# STM32F103_PCB.net
KiCad netlist of a schematic drawn in EAGLE
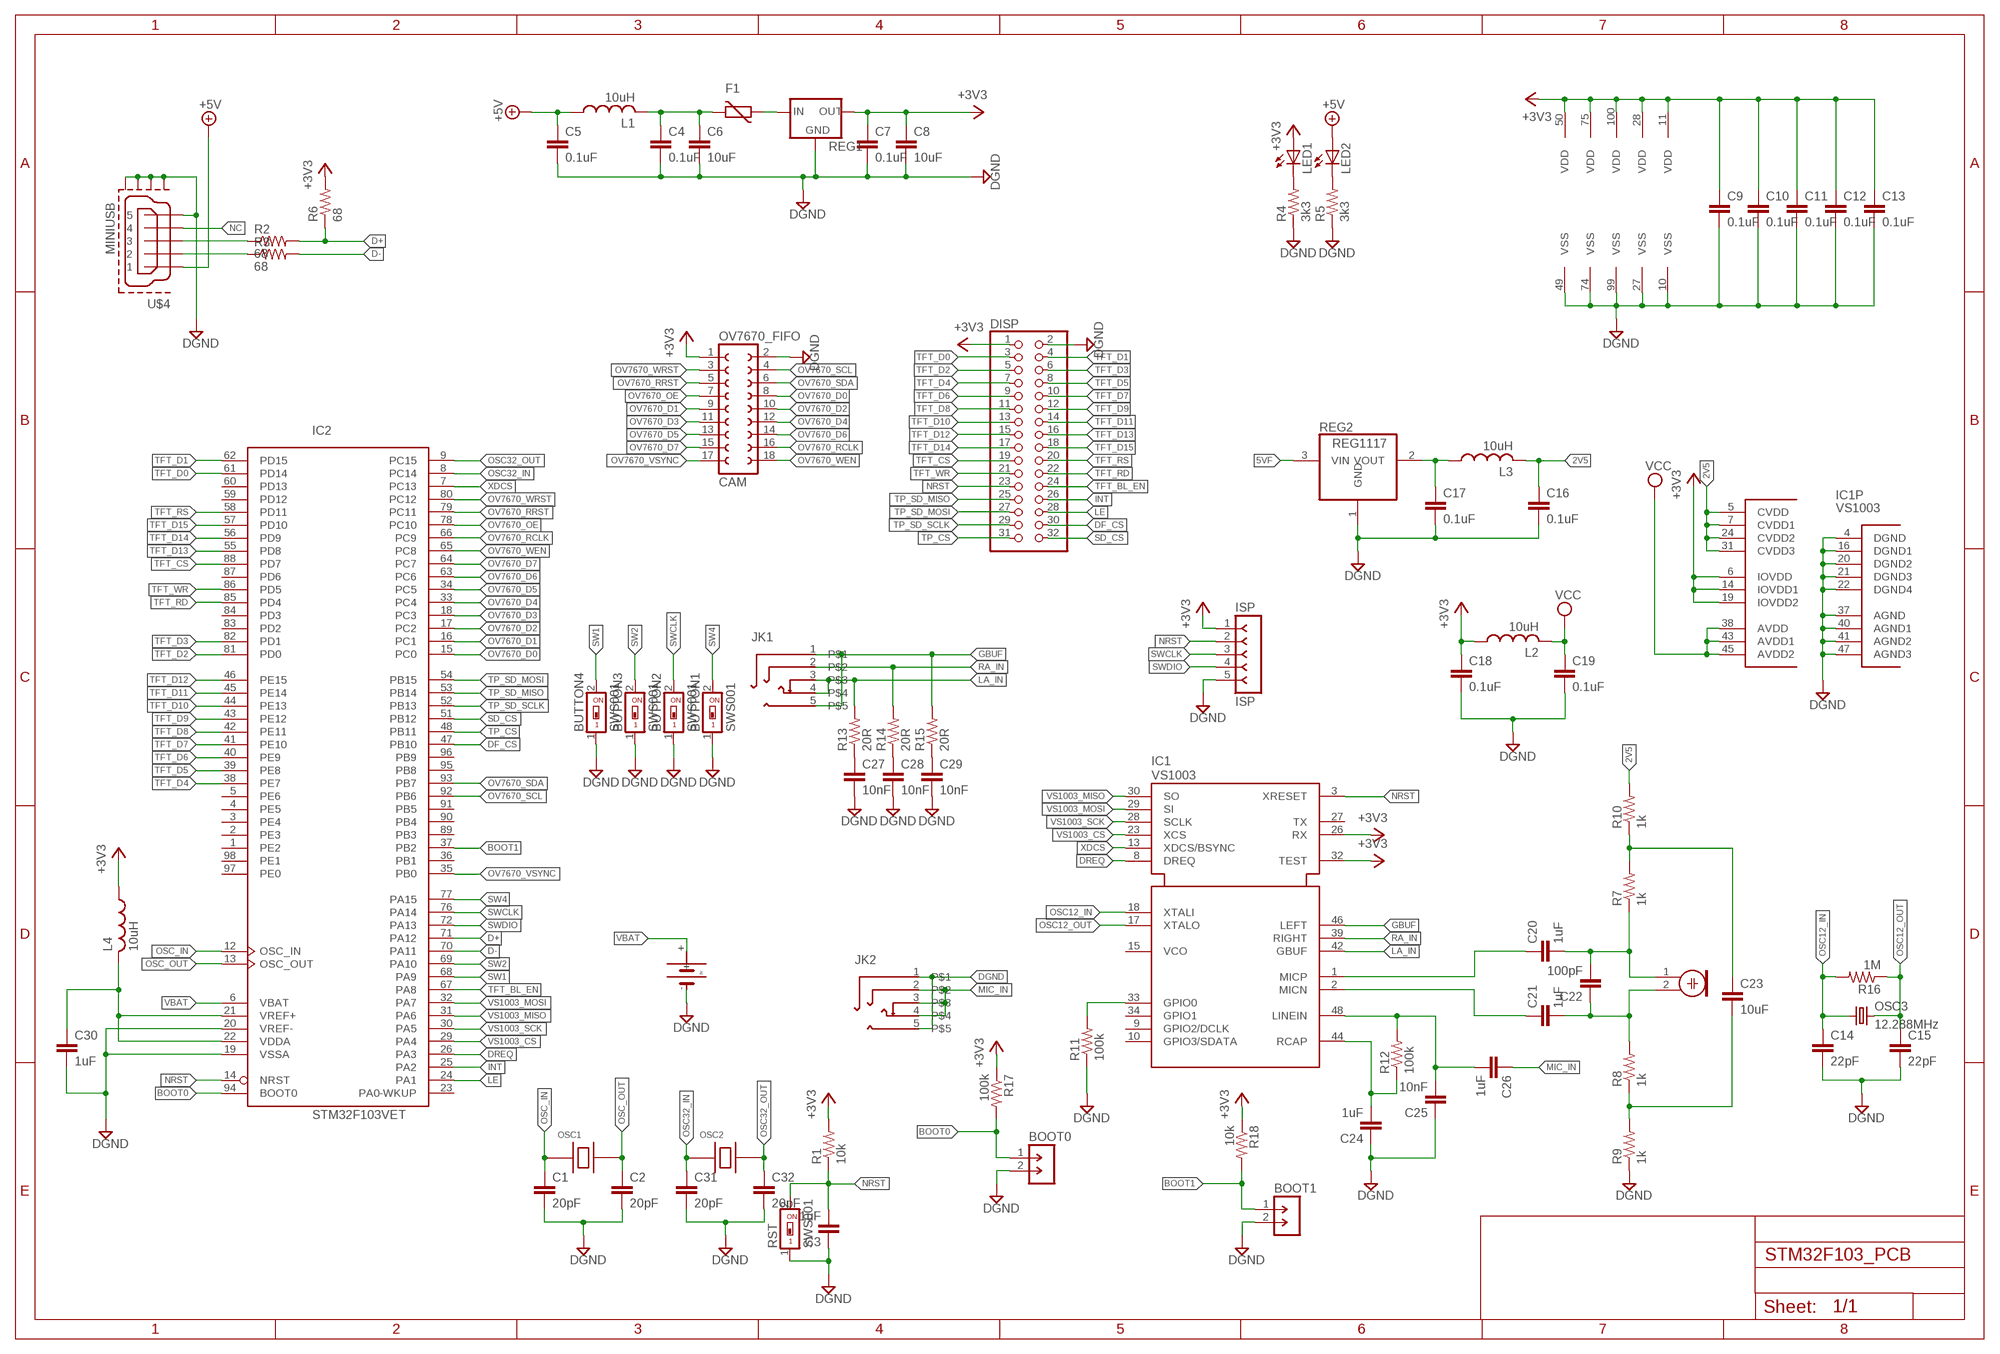
[diagram p0: schematic, sheet 1]

(export (version "E")
  (design (tool "Eeschema 10.0.6"))
  (components
    (comp (ref "BOOT0")
      (value "M-1X02-SIP-100-32")
      (footprint "eagle-import:SIP-100-02-32")
      (libsource (lib "eagle-import") (part "M-1X02-SIP-100-32"))
    )
    (comp (ref "BOOT1")
      (value "M-1X02-SIP-100-32")
      (footprint "eagle-import:SIP-100-02-32")
      (libsource (lib "eagle-import") (part "M-1X02-SIP-100-32"))
    )
    (comp (ref "BUTTON1")
      (value "SWS001")
      (footprint "eagle-import:SMS-001")
      (libsource (lib "eagle-import") (part "SWS001"))
    )
    (comp (ref "BUTTON2")
      (value "SWS001")
      (footprint "eagle-import:SMS-001")
      (libsource (lib "eagle-import") (part "SWS001"))
    )
    (comp (ref "BUTTON3")
      (value "SWS001")
      (footprint "eagle-import:SMS-001")
      (libsource (lib "eagle-import") (part "SWS001"))
    )
    (comp (ref "BUTTON4")
      (value "SWS001")
      (footprint "eagle-import:SMS-001")
      (libsource (lib "eagle-import") (part "SWS001"))
    )
    (comp (ref "C1")
      (value "20pF")
      (footprint "eagle-import:C1206")
      (libsource (lib "eagle-import") (part "C-EUC1206"))
    )
    (comp (ref "C2")
      (value "20pF")
      (footprint "eagle-import:C1206")
      (libsource (lib "eagle-import") (part "C-EUC1206"))
    )
    (comp (ref "C3")
      (value "1uF")
      (footprint "eagle-import:C1206")
      (libsource (lib "eagle-import") (part "C-EUC1206"))
    )
    (comp (ref "C4")
      (value "0.1uF")
      (footprint "eagle-import:C1206")
      (libsource (lib "eagle-import") (part "C-EUC1206"))
    )
    (comp (ref "C5")
      (value "0.1uF")
      (footprint "eagle-import:C1206")
      (libsource (lib "eagle-import") (part "C-EUC1206"))
    )
    (comp (ref "C6")
      (value "10uF")
      (footprint "eagle-import:C1206")
      (libsource (lib "eagle-import") (part "C-EUC1206"))
    )
    (comp (ref "C7")
      (value "0.1uF")
      (footprint "eagle-import:C1206")
      (libsource (lib "eagle-import") (part "C-EUC1206"))
    )
    (comp (ref "C8")
      (value "10uF")
      (footprint "eagle-import:C1206")
      (libsource (lib "eagle-import") (part "C-EUC1206"))
    )
    (comp (ref "C9")
      (value "0.1uF")
      (footprint "eagle-import:C1206")
      (libsource (lib "eagle-import") (part "C-EUC1206"))
    )
    (comp (ref "C10")
      (value "0.1uF")
      (footprint "eagle-import:C1206")
      (libsource (lib "eagle-import") (part "C-EUC1206"))
    )
    (comp (ref "C11")
      (value "0.1uF")
      (footprint "eagle-import:C1206")
      (libsource (lib "eagle-import") (part "C-EUC1206"))
    )
    (comp (ref "C12")
      (value "0.1uF")
      (footprint "eagle-import:C1206")
      (libsource (lib "eagle-import") (part "C-EUC1206"))
    )
    (comp (ref "C13")
      (value "0.1uF")
      (footprint "eagle-import:C1206")
      (libsource (lib "eagle-import") (part "C-EUC1206"))
    )
    (comp (ref "C14")
      (value "22pF")
      (footprint "eagle-import:C1206")
      (libsource (lib "eagle-import") (part "C-EUC1206"))
    )
    (comp (ref "C15")
      (value "22pF")
      (footprint "eagle-import:C1206")
      (libsource (lib "eagle-import") (part "C-EUC1206"))
    )
    (comp (ref "C16")
      (value "0.1uF")
      (footprint "eagle-import:C1206")
      (libsource (lib "eagle-import") (part "C-EUC1206"))
    )
    (comp (ref "C17")
      (value "0.1uF")
      (footprint "eagle-import:C1206")
      (libsource (lib "eagle-import") (part "C-EUC1206"))
    )
    (comp (ref "C18")
      (value "0.1uF")
      (footprint "eagle-import:C1206")
      (libsource (lib "eagle-import") (part "C-EUC1206"))
    )
    (comp (ref "C19")
      (value "0.1uF")
      (footprint "eagle-import:C1206")
      (libsource (lib "eagle-import") (part "C-EUC1206"))
    )
    (comp (ref "C20")
      (value "1uF")
      (footprint "eagle-import:C1206")
      (libsource (lib "eagle-import") (part "C-EUC1206"))
    )
    (comp (ref "C21")
      (value "1uF")
      (footprint "eagle-import:C1206")
      (libsource (lib "eagle-import") (part "C-EUC1206"))
    )
    (comp (ref "C22")
      (value "100pF")
      (footprint "eagle-import:C1206")
      (libsource (lib "eagle-import") (part "C-EUC1206"))
    )
    (comp (ref "C23")
      (value "10uF")
      (footprint "eagle-import:C1206")
      (libsource (lib "eagle-import") (part "C-EUC1206"))
    )
    (comp (ref "C24")
      (value "1uF")
      (footprint "eagle-import:C1206")
      (libsource (lib "eagle-import") (part "C-EUC1206"))
    )
    (comp (ref "C25")
      (value "10nF")
      (footprint "eagle-import:C1206")
      (libsource (lib "eagle-import") (part "C-EUC1206"))
    )
    (comp (ref "C26")
      (value "1uF")
      (footprint "eagle-import:C1206")
      (libsource (lib "eagle-import") (part "C-EUC1206"))
    )
    (comp (ref "C27")
      (value "10nF")
      (footprint "eagle-import:C1206")
      (libsource (lib "eagle-import") (part "C-EUC1206"))
    )
    (comp (ref "C28")
      (value "10nF")
      (footprint "eagle-import:C1206")
      (libsource (lib "eagle-import") (part "C-EUC1206"))
    )
    (comp (ref "C29")
      (value "10nF")
      (footprint "eagle-import:C1206")
      (libsource (lib "eagle-import") (part "C-EUC1206"))
    )
    (comp (ref "C30")
      (value "1uF")
      (footprint "eagle-import:C1206")
      (libsource (lib "eagle-import") (part "C-EUC1206"))
    )
    (comp (ref "C31")
      (value "20pF")
      (footprint "eagle-import:C1206")
      (libsource (lib "eagle-import") (part "C-EUC1206"))
    )
    (comp (ref "C32")
      (value "20pF")
      (footprint "eagle-import:C1206")
      (libsource (lib "eagle-import") (part "C-EUC1206"))
    )
    (comp (ref "CAM")
      (value "OV7670_FIFO")
      (footprint "eagle-import:FE09-2")
      (libsource (lib "eagle-import") (part "FE09-2"))
    )
    (comp (ref "DISP")
      (value "PINHD-2X16")
      (footprint "eagle-import:2X16")
      (libsource (lib "eagle-import") (part "PINHD-2X16"))
    )
    (comp (ref "F1")
      (value "VARISTORCN1206")
      (footprint "eagle-import:CT_CN1206")
      (libsource (lib "eagle-import") (part "VARISTORCN1206"))
    )
    (comp (ref "IC1")
      (value "VS1003")
      (footprint "eagle-import:LQFP48")
      (libsource (lib "eagle-import") (part "VS1003"))
    )
    (comp (ref "IC2")
      (value "STM32F103VET")
      (footprint "eagle-import:LQFP100")
      (libsource (lib "eagle-import") (part "STM32F103VTE"))
    )
    (comp (ref "ISP")
      (value "ISP")
      (footprint "eagle-import:SIP-100-05-40")
      (libsource (lib "eagle-import") (part "F-1X05-SIP-100-40"))
    )
    (comp (ref "JK1")
      (value "HEADPHONE_XXX1")
      (footprint "eagle-import:HEADPHONE_XXX1")
      (libsource (lib "eagle-import") (part "HEADPHONE_XXX1"))
    )
    (comp (ref "JK2")
      (value "HEADPHONE_XXX1")
      (footprint "eagle-import:HEADPHONE_XXX1")
      (libsource (lib "eagle-import") (part "HEADPHONE_XXX1"))
    )
    (comp (ref "L1")
      (value "10uH")
      (footprint "eagle-import:L3216C")
      (libsource (lib "eagle-import") (part "L-USL3216C"))
    )
    (comp (ref "L2")
      (value "10uH")
      (footprint "eagle-import:L3216C")
      (libsource (lib "eagle-import") (part "L-USL3216C"))
    )
    (comp (ref "L3")
      (value "10uH")
      (footprint "eagle-import:L3216C")
      (libsource (lib "eagle-import") (part "L-USL3216C"))
    )
    (comp (ref "L4")
      (value "10uH")
      (footprint "eagle-import:L3216C")
      (libsource (lib "eagle-import") (part "L-USL3216C"))
    )
    (comp (ref "LED1")
      (value "LEDSML1206")
      (footprint "eagle-import:SML1206")
      (libsource (lib "eagle-import") (part "LEDSML1206"))
    )
    (comp (ref "LED2")
      (value "LEDSML1206")
      (footprint "eagle-import:SML1206")
      (libsource (lib "eagle-import") (part "LEDSML1206"))
    )
    (comp (ref "MIC")
      (value "ELECTRET_MICROPHON-WM-61A")
      (footprint "eagle-import:WM-61A")
      (libsource (lib "eagle-import") (part "ELECTRET_MICROPHON-WM-61A"))
    )
    (comp (ref "OSC1")
      (value "8.0MHz")
      (footprint "eagle-import:IQG7050B")
      (libsource (lib "eagle-import") (part "SMCE-7050"))
    )
    (comp (ref "OSC2")
      (value "32.768kHz")
      (footprint "eagle-import:IQG5032A")
      (libsource (lib "eagle-import") (part "SMAQ-5032A"))
    )
    (comp (ref "OSC3")
      (value "12.288MHz")
      (footprint "eagle-import:HC49UP")
      (libsource (lib "eagle-import") (part "CRYSTALHC49UP"))
    )
    (comp (ref "R1")
      (value "10k")
      (footprint "eagle-import:R1206")
      (libsource (lib "eagle-import") (part "R-US_R1206"))
    )
    (comp (ref "R2")
      (value "68")
      (footprint "eagle-import:R1206")
      (libsource (lib "eagle-import") (part "R-US_R1206"))
    )
    (comp (ref "R3")
      (value "68")
      (footprint "eagle-import:R1206")
      (libsource (lib "eagle-import") (part "R-US_R1206"))
    )
    (comp (ref "R4")
      (value "3k3")
      (footprint "eagle-import:R1206")
      (libsource (lib "eagle-import") (part "R-US_R1206"))
    )
    (comp (ref "R5")
      (value "3k3")
      (footprint "eagle-import:R1206")
      (libsource (lib "eagle-import") (part "R-US_R1206"))
    )
    (comp (ref "R6")
      (value "68")
      (footprint "eagle-import:R1206")
      (libsource (lib "eagle-import") (part "R-US_R1206"))
    )
    (comp (ref "R7")
      (value "1k")
      (footprint "eagle-import:R1206")
      (libsource (lib "eagle-import") (part "R-US_R1206"))
    )
    (comp (ref "R8")
      (value "1k")
      (footprint "eagle-import:R1206")
      (libsource (lib "eagle-import") (part "R-US_R1206"))
    )
    (comp (ref "R9")
      (value "1k")
      (footprint "eagle-import:R1206")
      (libsource (lib "eagle-import") (part "R-US_R1206"))
    )
    (comp (ref "R10")
      (value "1k")
      (footprint "eagle-import:R1206")
      (libsource (lib "eagle-import") (part "R-US_R1206"))
    )
    (comp (ref "R11")
      (value "100k")
      (footprint "eagle-import:R1206")
      (libsource (lib "eagle-import") (part "R-US_R1206"))
    )
    (comp (ref "R12")
      (value "100k")
      (footprint "eagle-import:R1206")
      (libsource (lib "eagle-import") (part "R-US_R1206"))
    )
    (comp (ref "R13")
      (value "20R")
      (footprint "eagle-import:R1206")
      (libsource (lib "eagle-import") (part "R-US_R1206"))
    )
    (comp (ref "R14")
      (value "20R")
      (footprint "eagle-import:R1206")
      (libsource (lib "eagle-import") (part "R-US_R1206"))
    )
    (comp (ref "R15")
      (value "20R")
      (footprint "eagle-import:R1206")
      (libsource (lib "eagle-import") (part "R-US_R1206"))
    )
    (comp (ref "R16")
      (value "1M")
      (footprint "eagle-import:R1206")
      (libsource (lib "eagle-import") (part "R-US_R1206"))
    )
    (comp (ref "R17")
      (value "100k")
      (footprint "eagle-import:R1206")
      (libsource (lib "eagle-import") (part "R-US_R1206"))
    )
    (comp (ref "R18")
      (value "10k")
      (footprint "eagle-import:R1206")
      (libsource (lib "eagle-import") (part "R-US_R1206"))
    )
    (comp (ref "REG1")
      (value "XC63FPM")
      (footprint "eagle-import:SOT23")
      (libsource (lib "eagle-import") (part "XC63FPM"))
    )
    (comp (ref "REG2")
      (value "REG1117")
      (footprint "eagle-import:SOT223")
      (libsource (lib "eagle-import") (part "REG1117"))
    )
    (comp (ref "RST")
      (value "SWS001")
      (footprint "eagle-import:SMS-001")
      (libsource (lib "eagle-import") (part "SWS001"))
    )
    (comp (ref "U$1")
      (value "1220BATTERY_SF")
      (footprint "eagle-import:1220BATTERY")
      (libsource (lib "eagle-import") (part "1220BATTERY_SF"))
    )
    (comp (ref "U$4")
      (value "MINIUSB")
      (footprint "eagle-import:MK5P")
      (libsource (lib "eagle-import") (part "MINIUSB"))
    )
  )
  (nets
    (net (code "1") (name "+3V3") (class "Default")
      (node (ref "C10") (pin "1") (pinfunction "1_1") (pintype "passive"))
      (node (ref "C11") (pin "1") (pinfunction "1_1") (pintype "passive"))
      (node (ref "C12") (pin "1") (pinfunction "1_1") (pintype "passive"))
      (node (ref "C13") (pin "1") (pinfunction "1_1") (pintype "passive"))
      (node (ref "C18") (pin "1") (pinfunction "1_1") (pintype "passive"))
      (node (ref "C7") (pin "1") (pinfunction "1_1") (pintype "passive"))
      (node (ref "C8") (pin "1") (pinfunction "1_1") (pintype "passive"))
      (node (ref "C9") (pin "1") (pinfunction "1_1") (pintype "passive"))
      (node (ref "CAM") (pin "1") (pinfunction "1_1") (pintype "passive"))
      (node (ref "DISP") (pin "1") (pinfunction "1_1") (pintype "passive"))
      (node (ref "IC1") (pin "14") (pinfunction "IOVDD1_14") (pintype "power_in"))
      (node (ref "IC1") (pin "19") (pinfunction "IOVDD2_19") (pintype "power_in"))
      (node (ref "IC1") (pin "26") (pinfunction "RX_26") (pintype "bidirectional"))
      (node (ref "IC1") (pin "32") (pinfunction "TEST_32") (pintype "bidirectional"))
      (node (ref "IC1") (pin "6") (pinfunction "IOVDD_6") (pintype "power_in"))
      (node (ref "IC2") (pin "100") (pinfunction "VDD_100") (pintype "power_in"))
      (node (ref "IC2") (pin "11") (pinfunction "VDD_11") (pintype "power_in"))
      (node (ref "IC2") (pin "28") (pinfunction "VDD_28") (pintype "power_in"))
      (node (ref "IC2") (pin "50") (pinfunction "VDD_50") (pintype "power_in"))
      (node (ref "IC2") (pin "75") (pinfunction "VDD_75") (pintype "power_in"))
      (node (ref "ISP") (pin "1") (pinfunction "1_1") (pintype "passive"))
      (node (ref "L2") (pin "1") (pinfunction "1_1") (pintype "passive"))
      (node (ref "L4") (pin "1") (pinfunction "1_1") (pintype "passive"))
      (node (ref "LED1") (pin "A") (pinfunction "A_A") (pintype "passive"))
      (node (ref "R1") (pin "2") (pinfunction "2_2") (pintype "passive"))
      (node (ref "R17") (pin "1") (pinfunction "1_1") (pintype "passive"))
      (node (ref "R18") (pin "1") (pinfunction "1_1") (pintype "passive"))
      (node (ref "R6") (pin "2") (pinfunction "2_2") (pintype "passive"))
      (node (ref "REG1") (pin "2") (pinfunction "OUT_2") (pintype "passive"))
    )
    (net (code "2") (name "+5V") (class "Default")
      (node (ref "C5") (pin "1") (pinfunction "1_1") (pintype "passive"))
      (node (ref "L1") (pin "1") (pinfunction "1_1") (pintype "passive"))
      (node (ref "LED2") (pin "A") (pinfunction "A_A") (pintype "passive"))
      (node (ref "U$4") (pin "1") (pinfunction "1_1") (pintype "input"))
    )
    (net (code "3") (name "2V5") (class "Default")
      (node (ref "C16") (pin "1") (pinfunction "1_1") (pintype "passive"))
      (node (ref "IC1") (pin "24") (pinfunction "CVDD2_24") (pintype "power_in"))
      (node (ref "IC1") (pin "31") (pinfunction "CVDD3_31") (pintype "power_in"))
      (node (ref "IC1") (pin "5") (pinfunction "CVDD_5") (pintype "power_in"))
      (node (ref "IC1") (pin "7") (pinfunction "CVDD1_7") (pintype "power_in"))
      (node (ref "L3") (pin "2") (pinfunction "2_2") (pintype "passive"))
      (node (ref "R10") (pin "2") (pinfunction "2_2") (pintype "passive"))
    )
    (net (code "4") (name "5VF") (class "Default")
      (node (ref "F1") (pin "1") (pinfunction "1_1") (pintype "passive"))
      (node (ref "REG1") (pin "3") (pinfunction "IN_3") (pintype "input"))
      (node (ref "REG2") (pin "3") (pinfunction "VIN_3") (pintype "input"))
    )
    (net (code "5") (name "BOOT0") (class "Default")
      (node (ref "BOOT0") (pin "1") (pinfunction "1_1") (pintype "passive"))
      (node (ref "IC2") (pin "94") (pinfunction "BOOT0_94") (pintype "input"))
      (node (ref "R17") (pin "2") (pinfunction "2_2") (pintype "passive"))
    )
    (net (code "6") (name "BOOT1") (class "Default")
      (node (ref "BOOT1") (pin "1") (pinfunction "1_1") (pintype "passive"))
      (node (ref "IC2") (pin "37") (pinfunction "PB2_37") (pintype "bidirectional"))
      (node (ref "R18") (pin "2") (pinfunction "2_2") (pintype "passive"))
    )
    (net (code "7") (name "D+") (class "Default")
      (node (ref "IC2") (pin "71") (pinfunction "PA12_71") (pintype "bidirectional"))
      (node (ref "R2") (pin "2") (pinfunction "2_2") (pintype "passive"))
      (node (ref "R6") (pin "1") (pinfunction "1_1") (pintype "passive"))
    )
    (net (code "8") (name "D-") (class "Default")
      (node (ref "IC2") (pin "70") (pinfunction "PA11_70") (pintype "bidirectional"))
      (node (ref "R3") (pin "2") (pinfunction "2_2") (pintype "passive"))
    )
    (net (code "9") (name "DF_CS") (class "Default")
      (node (ref "DISP") (pin "30") (pinfunction "30_30") (pintype "passive"))
      (node (ref "IC2") (pin "47") (pinfunction "PB10_47") (pintype "bidirectional"))
    )
    (net (code "10") (name "DGND") (class "Default")
      (node (ref "BOOT0") (pin "2") (pinfunction "2_2") (pintype "passive"))
      (node (ref "BOOT1") (pin "2") (pinfunction "2_2") (pintype "passive"))
      (node (ref "BUTTON1") (pin "1") (pinfunction "1_1") (pintype "passive"))
      (node (ref "BUTTON2") (pin "1") (pinfunction "1_1") (pintype "passive"))
      (node (ref "BUTTON3") (pin "1") (pinfunction "1_1") (pintype "passive"))
      (node (ref "BUTTON4") (pin "1") (pinfunction "1_1") (pintype "passive"))
      (node (ref "C1") (pin "2") (pinfunction "2_2") (pintype "passive"))
      (node (ref "C10") (pin "2") (pinfunction "2_2") (pintype "passive"))
      (node (ref "C11") (pin "2") (pinfunction "2_2") (pintype "passive"))
      (node (ref "C12") (pin "2") (pinfunction "2_2") (pintype "passive"))
      (node (ref "C13") (pin "2") (pinfunction "2_2") (pintype "passive"))
      (node (ref "C14") (pin "2") (pinfunction "2_2") (pintype "passive"))
      (node (ref "C15") (pin "2") (pinfunction "2_2") (pintype "passive"))
      (node (ref "C16") (pin "2") (pinfunction "2_2") (pintype "passive"))
      (node (ref "C17") (pin "2") (pinfunction "2_2") (pintype "passive"))
      (node (ref "C18") (pin "2") (pinfunction "2_2") (pintype "passive"))
      (node (ref "C19") (pin "2") (pinfunction "2_2") (pintype "passive"))
      (node (ref "C2") (pin "2") (pinfunction "2_2") (pintype "passive"))
      (node (ref "C24") (pin "1") (pinfunction "1_1") (pintype "passive"))
      (node (ref "C25") (pin "1") (pinfunction "1_1") (pintype "passive"))
      (node (ref "C27") (pin "2") (pinfunction "2_2") (pintype "passive"))
      (node (ref "C28") (pin "2") (pinfunction "2_2") (pintype "passive"))
      (node (ref "C29") (pin "2") (pinfunction "2_2") (pintype "passive"))
      (node (ref "C3") (pin "1") (pinfunction "1_1") (pintype "passive"))
      (node (ref "C30") (pin "2") (pinfunction "2_2") (pintype "passive"))
      (node (ref "C31") (pin "2") (pinfunction "2_2") (pintype "passive"))
      (node (ref "C32") (pin "2") (pinfunction "2_2") (pintype "passive"))
      (node (ref "C4") (pin "2") (pinfunction "2_2") (pintype "passive"))
      (node (ref "C5") (pin "2") (pinfunction "2_2") (pintype "passive"))
      (node (ref "C6") (pin "2") (pinfunction "2_2") (pintype "passive"))
      (node (ref "C7") (pin "2") (pinfunction "2_2") (pintype "passive"))
      (node (ref "C8") (pin "2") (pinfunction "2_2") (pintype "passive"))
      (node (ref "C9") (pin "2") (pinfunction "2_2") (pintype "passive"))
      (node (ref "CAM") (pin "2") (pinfunction "2_2") (pintype "passive"))
      (node (ref "DISP") (pin "2") (pinfunction "2_2") (pintype "passive"))
      (node (ref "IC1") (pin "16") (pinfunction "DGND1_16") (pintype "power_in"))
      (node (ref "IC1") (pin "20") (pinfunction "DGND2_20") (pintype "power_in"))
      (node (ref "IC1") (pin "21") (pinfunction "DGND3_21") (pintype "power_in"))
      (node (ref "IC1") (pin "22") (pinfunction "DGND4_22") (pintype "power_in"))
      (node (ref "IC1") (pin "37") (pinfunction "AGND_37") (pintype "power_in"))
      (node (ref "IC1") (pin "4") (pinfunction "DGND_4") (pintype "power_in"))
      (node (ref "IC1") (pin "40") (pinfunction "AGND1_40") (pintype "power_in"))
      (node (ref "IC1") (pin "41") (pinfunction "AGND2_41") (pintype "power_in"))
      (node (ref "IC1") (pin "47") (pinfunction "AGND3_47") (pintype "power_in"))
      (node (ref "IC2") (pin "10") (pinfunction "VSS_10") (pintype "power_in"))
      (node (ref "IC2") (pin "19") (pinfunction "VSSA_19") (pintype "power_in"))
      (node (ref "IC2") (pin "20") (pinfunction "VREF-_20") (pintype "power_in"))
      (node (ref "IC2") (pin "27") (pinfunction "VSS_27") (pintype "power_in"))
      (node (ref "IC2") (pin "49") (pinfunction "VSS_49") (pintype "power_in"))
      (node (ref "IC2") (pin "74") (pinfunction "VSS_74") (pintype "power_in"))
      (node (ref "IC2") (pin "99") (pinfunction "VSS_99") (pintype "power_in"))
      (node (ref "ISP") (pin "5") (pinfunction "5_5") (pintype "passive"))
      (node (ref "JK2") (pin "1") (pinfunction "P$1_1") (pintype "bidirectional"))
      (node (ref "JK2") (pin "5") (pinfunction "P$5_5") (pintype "bidirectional"))
      (node (ref "R11") (pin "1") (pinfunction "1_1") (pintype "passive"))
      (node (ref "R4") (pin "1") (pinfunction "1_1") (pintype "passive"))
      (node (ref "R5") (pin "1") (pinfunction "1_1") (pintype "passive"))
      (node (ref "R9") (pin "1") (pinfunction "1_1") (pintype "passive"))
      (node (ref "REG1") (pin "1") (pinfunction "GND_1") (pintype "input"))
      (node (ref "REG2") (pin "1") (pinfunction "GND_1") (pintype "power_in"))
      (node (ref "RST") (pin "1") (pinfunction "1_1") (pintype "passive"))
      (node (ref "U$1") (pin "-") (pinfunction "-_-") (pintype "bidirectional"))
      (node (ref "U$4") (pin "5") (pinfunction "5_5") (pintype "input"))
      (node (ref "U$4") (pin "P$1") (pinfunction "GND1_P$1") (pintype "bidirectional"))
      (node (ref "U$4") (pin "P$2") (pinfunction "GND2_P$2") (pintype "bidirectional"))
      (node (ref "U$4") (pin "P$6") (pinfunction "GND3_P$6") (pintype "bidirectional"))
      (node (ref "U$4") (pin "P$7") (pinfunction "GND4_P$7") (pintype "bidirectional"))
    )
    (net (code "11") (name "DREQ") (class "Default")
      (node (ref "IC1") (pin "8") (pinfunction "DREQ_8") (pintype "bidirectional"))
      (node (ref "IC2") (pin "26") (pinfunction "PA3_26") (pintype "bidirectional"))
    )
    (net (code "12") (name "GBUF") (class "Default")
      (node (ref "IC1") (pin "46") (pinfunction "LEFT_46") (pintype "bidirectional"))
      (node (ref "JK1") (pin "1") (pinfunction "P$1_1") (pintype "bidirectional"))
      (node (ref "JK1") (pin "5") (pinfunction "P$5_5") (pintype "bidirectional"))
      (node (ref "R15") (pin "2") (pinfunction "2_2") (pintype "passive"))
    )
    (net (code "13") (name "INT") (class "Default")
      (node (ref "DISP") (pin "26") (pinfunction "26_26") (pintype "passive"))
      (node (ref "IC2") (pin "25") (pinfunction "PA2_25") (pintype "bidirectional"))
    )
    (net (code "14") (name "LA_IN") (class "Default")
      (node (ref "IC1") (pin "42") (pinfunction "GBUF_42") (pintype "bidirectional"))
      (node (ref "JK1") (pin "3") (pinfunction "P$3_3") (pintype "bidirectional"))
      (node (ref "JK1") (pin "4") (pinfunction "P$4_4") (pintype "bidirectional"))
      (node (ref "R13") (pin "2") (pinfunction "2_2") (pintype "passive"))
    )
    (net (code "15") (name "LE") (class "Default")
      (node (ref "DISP") (pin "28") (pinfunction "28_28") (pintype "passive"))
      (node (ref "IC2") (pin "24") (pinfunction "PA1_24") (pintype "bidirectional"))
    )
    (net (code "16") (name "MIC_IN") (class "Default")
      (node (ref "C26") (pin "1") (pinfunction "1_1") (pintype "passive"))
      (node (ref "JK2") (pin "2") (pinfunction "P$2_2") (pintype "bidirectional"))
      (node (ref "JK2") (pin "3") (pinfunction "P$3_3") (pintype "bidirectional"))
      (node (ref "JK2") (pin "4") (pinfunction "P$4_4") (pintype "bidirectional"))
    )
    (net (code "17") (name "NC") (class "Default")
      (node (ref "U$4") (pin "4") (pinfunction "4_4") (pintype "input"))
    )
    (net (code "18") (name "NRST") (class "Default")
      (node (ref "C3") (pin "2") (pinfunction "2_2") (pintype "passive"))
      (node (ref "DISP") (pin "23") (pinfunction "23_23") (pintype "passive"))
      (node (ref "IC1") (pin "3") (pinfunction "XRESET_3") (pintype "bidirectional"))
      (node (ref "IC2") (pin "14") (pinfunction "NRST_14") (pintype "bidirectional"))
      (node (ref "ISP") (pin "2") (pinfunction "2_2") (pintype "passive"))
      (node (ref "R1") (pin "1") (pinfunction "1_1") (pintype "passive"))
      (node (ref "RST") (pin "2") (pinfunction "2_2") (pintype "passive"))
    )
    (net (code "19") (name "Net-(C4-Pad1)") (class "Default")
      (node (ref "C4") (pin "1") (pinfunction "1_1") (pintype "passive"))
      (node (ref "C6") (pin "1") (pinfunction "1_1") (pintype "passive"))
      (node (ref "F1") (pin "2") (pinfunction "2_2") (pintype "passive"))
      (node (ref "L1") (pin "2") (pinfunction "2_2") (pintype "passive"))
    )
    (net (code "20") (name "Net-(C20-Pad2)") (class "Default")
      (node (ref "C20") (pin "2") (pinfunction "2_2") (pintype "passive"))
      (node (ref "C22") (pin "2") (pinfunction "2_2") (pintype "passive"))
      (node (ref "MIC") (pin "1") (pinfunction "1_1") (pintype "passive"))
      (node (ref "R7") (pin "1") (pinfunction "1_1") (pintype "passive"))
    )
    (net (code "21") (name "Net-(C21-Pad2)") (class "Default")
      (node (ref "C21") (pin "2") (pinfunction "2_2") (pintype "passive"))
      (node (ref "C22") (pin "1") (pinfunction "1_1") (pintype "passive"))
      (node (ref "MIC") (pin "2") (pinfunction "2_2") (pintype "passive"))
      (node (ref "R8") (pin "2") (pinfunction "2_2") (pintype "passive"))
    )
    (net (code "22") (name "Net-(C23-Pad1)") (class "Default")
      (node (ref "C23") (pin "1") (pinfunction "1_1") (pintype "passive"))
      (node (ref "R10") (pin "1") (pinfunction "1_1") (pintype "passive"))
      (node (ref "R7") (pin "2") (pinfunction "2_2") (pintype "passive"))
    )
    (net (code "23") (name "Net-(C23-Pad2)") (class "Default")
      (node (ref "C23") (pin "2") (pinfunction "2_2") (pintype "passive"))
      (node (ref "R8") (pin "1") (pinfunction "1_1") (pintype "passive"))
      (node (ref "R9") (pin "2") (pinfunction "2_2") (pintype "passive"))
    )
    (net (code "24") (name "Net-(C27-Pad1)") (class "Default")
      (node (ref "C27") (pin "1") (pinfunction "1_1") (pintype "passive"))
      (node (ref "R13") (pin "1") (pinfunction "1_1") (pintype "passive"))
    )
    (net (code "25") (name "Net-(C28-Pad1)") (class "Default")
      (node (ref "C28") (pin "1") (pinfunction "1_1") (pintype "passive"))
      (node (ref "R14") (pin "1") (pinfunction "1_1") (pintype "passive"))
    )
    (net (code "26") (name "Net-(C29-Pad1)") (class "Default")
      (node (ref "C29") (pin "1") (pinfunction "1_1") (pintype "passive"))
      (node (ref "R15") (pin "1") (pinfunction "1_1") (pintype "passive"))
    )
    (net (code "27") (name "Net-(IC1A-GPIO0)") (class "Default")
      (node (ref "IC1") (pin "33") (pinfunction "GPIO0_33") (pintype "bidirectional"))
      (node (ref "R11") (pin "2") (pinfunction "2_2") (pintype "passive"))
    )
    (net (code "28") (name "Net-(IC1A-LINEIN)") (class "Default")
      (node (ref "C25") (pin "2") (pinfunction "2_2") (pintype "passive"))
      (node (ref "C26") (pin "2") (pinfunction "2_2") (pintype "passive"))
      (node (ref "IC1") (pin "48") (pinfunction "LINEIN_48") (pintype "bidirectional"))
      (node (ref "R12") (pin "2") (pinfunction "2_2") (pintype "passive"))
    )
    (net (code "29") (name "Net-(IC1A-MICN)") (class "Default")
      (node (ref "C21") (pin "1") (pinfunction "1_1") (pintype "passive"))
      (node (ref "IC1") (pin "2") (pinfunction "MICN_2") (pintype "bidirectional"))
    )
    (net (code "30") (name "Net-(IC1A-MICP)") (class "Default")
      (node (ref "C20") (pin "1") (pinfunction "1_1") (pintype "passive"))
      (node (ref "IC1") (pin "1") (pinfunction "MICP_1") (pintype "bidirectional"))
    )
    (net (code "31") (name "Net-(IC1A-RCAP)") (class "Default")
      (node (ref "C24") (pin "2") (pinfunction "2_2") (pintype "passive"))
      (node (ref "IC1") (pin "44") (pinfunction "RCAP_44") (pintype "bidirectional"))
      (node (ref "R12") (pin "1") (pinfunction "1_1") (pintype "passive"))
    )
    (net (code "32") (name "Net-(IC2A-VDDA)") (class "Default")
      (node (ref "C30") (pin "1") (pinfunction "1_1") (pintype "passive"))
      (node (ref "IC2") (pin "21") (pinfunction "VREF+_21") (pintype "power_in"))
      (node (ref "IC2") (pin "22") (pinfunction "VDDA_22") (pintype "power_in"))
      (node (ref "L4") (pin "2") (pinfunction "2_2") (pintype "passive"))
    )
    (net (code "33") (name "Net-(LED1-PadC)") (class "Default")
      (node (ref "LED1") (pin "C") (pinfunction "C_C") (pintype "passive"))
      (node (ref "R4") (pin "2") (pinfunction "2_2") (pintype "passive"))
    )
    (net (code "34") (name "Net-(LED2-PadC)") (class "Default")
      (node (ref "LED2") (pin "C") (pinfunction "C_C") (pintype "passive"))
      (node (ref "R5") (pin "2") (pinfunction "2_2") (pintype "passive"))
    )
    (net (code "35") (name "Net-(R2-Pad1)") (class "Default")
      (node (ref "R2") (pin "1") (pinfunction "1_1") (pintype "passive"))
      (node (ref "U$4") (pin "3") (pinfunction "3_3") (pintype "input"))
    )
    (net (code "36") (name "Net-(R3-Pad1)") (class "Default")
      (node (ref "R3") (pin "1") (pinfunction "1_1") (pintype "passive"))
      (node (ref "U$4") (pin "2") (pinfunction "2_2") (pintype "input"))
    )
    (net (code "37") (name "Net-(REG2-VOUT)") (class "Default")
      (node (ref "C17") (pin "1") (pinfunction "1_1") (pintype "passive"))
      (node (ref "L3") (pin "1") (pinfunction "1_1") (pintype "passive"))
      (node (ref "REG2") (pin "2") (pinfunction "VOUT_2") (pintype "output"))
    )
    (net (code "38") (name "OSC12_IN") (class "Default")
      (node (ref "C14") (pin "1") (pinfunction "1_1") (pintype "passive"))
      (node (ref "IC1") (pin "18") (pinfunction "XTALI_18") (pintype "bidirectional"))
      (node (ref "OSC3") (pin "1") (pinfunction "1_1") (pintype "passive"))
      (node (ref "R16") (pin "2") (pinfunction "2_2") (pintype "passive"))
    )
    (net (code "39") (name "OSC12_OUT") (class "Default")
      (node (ref "C15") (pin "1") (pinfunction "1_1") (pintype "passive"))
      (node (ref "IC1") (pin "17") (pinfunction "XTALO_17") (pintype "bidirectional"))
      (node (ref "OSC3") (pin "2") (pinfunction "2_2") (pintype "passive"))
      (node (ref "R16") (pin "1") (pinfunction "1_1") (pintype "passive"))
    )
    (net (code "40") (name "OSC32_IN") (class "Default")
      (node (ref "C31") (pin "1") (pinfunction "1_1") (pintype "passive"))
      (node (ref "IC2") (pin "8") (pinfunction "PC14_8") (pintype "bidirectional"))
      (node (ref "OSC2") (pin "P$1") (pinfunction "PIN1_P$1") (pintype "bidirectional"))
    )
    (net (code "41") (name "OSC32_OUT") (class "Default")
      (node (ref "C32") (pin "1") (pinfunction "1_1") (pintype "passive"))
      (node (ref "IC2") (pin "9") (pinfunction "PC15_9") (pintype "bidirectional"))
      (node (ref "OSC2") (pin "P$2") (pinfunction "PIN2_P$2") (pintype "bidirectional"))
    )
    (net (code "42") (name "OSC_IN") (class "Default")
      (node (ref "C1") (pin "1") (pinfunction "1_1") (pintype "passive"))
      (node (ref "IC2") (pin "12") (pinfunction "OSC_IN_12") (pintype "bidirectional"))
      (node (ref "OSC1") (pin "P$1") (pinfunction "PIN1_P$1") (pintype "bidirectional"))
    )
    (net (code "43") (name "OSC_OUT") (class "Default")
      (node (ref "C2") (pin "1") (pinfunction "1_1") (pintype "passive"))
      (node (ref "IC2") (pin "13") (pinfunction "OSC_OUT_13") (pintype "bidirectional"))
      (node (ref "OSC1") (pin "P$3") (pinfunction "PIN2_P$3") (pintype "bidirectional"))
    )
    (net (code "44") (name "OV7670_D0") (class "Default")
      (node (ref "CAM") (pin "8") (pinfunction "8_8") (pintype "passive"))
      (node (ref "IC2") (pin "15") (pinfunction "PC0_15") (pintype "bidirectional"))
    )
    (net (code "45") (name "OV7670_D1") (class "Default")
      (node (ref "CAM") (pin "9") (pinfunction "9_9") (pintype "passive"))
      (node (ref "IC2") (pin "16") (pinfunction "PC1_16") (pintype "bidirectional"))
    )
    (net (code "46") (name "OV7670_D2") (class "Default")
      (node (ref "CAM") (pin "10") (pinfunction "10_10") (pintype "passive"))
      (node (ref "IC2") (pin "17") (pinfunction "PC2_17") (pintype "bidirectional"))
    )
    (net (code "47") (name "OV7670_D3") (class "Default")
      (node (ref "CAM") (pin "11") (pinfunction "11_11") (pintype "passive"))
      (node (ref "IC2") (pin "18") (pinfunction "PC3_18") (pintype "bidirectional"))
    )
    (net (code "48") (name "OV7670_D4") (class "Default")
      (node (ref "CAM") (pin "12") (pinfunction "12_12") (pintype "passive"))
      (node (ref "IC2") (pin "33") (pinfunction "PC4_33") (pintype "bidirectional"))
    )
    (net (code "49") (name "OV7670_D5") (class "Default")
      (node (ref "CAM") (pin "13") (pinfunction "13_13") (pintype "passive"))
      (node (ref "IC2") (pin "34") (pinfunction "PC5_34") (pintype "bidirectional"))
    )
    (net (code "50") (name "OV7670_D6") (class "Default")
      (node (ref "CAM") (pin "14") (pinfunction "14_14") (pintype "passive"))
      (node (ref "IC2") (pin "63") (pinfunction "PC6_63") (pintype "bidirectional"))
    )
    (net (code "51") (name "OV7670_D7") (class "Default")
      (node (ref "CAM") (pin "15") (pinfunction "15_15") (pintype "passive"))
      (node (ref "IC2") (pin "64") (pinfunction "PC7_64") (pintype "bidirectional"))
    )
    (net (code "52") (name "OV7670_OE") (class "Default")
      (node (ref "CAM") (pin "7") (pinfunction "7_7") (pintype "passive"))
      (node (ref "IC2") (pin "78") (pinfunction "PC10_78") (pintype "bidirectional"))
    )
    (net (code "53") (name "OV7670_RCLK") (class "Default")
      (node (ref "CAM") (pin "16") (pinfunction "16_16") (pintype "passive"))
      (node (ref "IC2") (pin "66") (pinfunction "PC9_66") (pintype "bidirectional"))
    )
    (net (code "54") (name "OV7670_RRST") (class "Default")
      (node (ref "CAM") (pin "5") (pinfunction "5_5") (pintype "passive"))
      (node (ref "IC2") (pin "79") (pinfunction "PC11_79") (pintype "bidirectional"))
    )
    (net (code "55") (name "OV7670_SCL") (class "Default")
      (node (ref "CAM") (pin "4") (pinfunction "4_4") (pintype "passive"))
      (node (ref "IC2") (pin "92") (pinfunction "PB6_92") (pintype "bidirectional"))
    )
    (net (code "56") (name "OV7670_SDA") (class "Default")
      (node (ref "CAM") (pin "6") (pinfunction "6_6") (pintype "passive"))
      (node (ref "IC2") (pin "93") (pinfunction "PB7_93") (pintype "bidirectional"))
    )
    (net (code "57") (name "OV7670_VSYNC") (class "Default")
      (node (ref "CAM") (pin "17") (pinfunction "17_17") (pintype "passive"))
      (node (ref "IC2") (pin "35") (pinfunction "PB0_35") (pintype "bidirectional"))
    )
    (net (code "58") (name "OV7670_WEN") (class "Default")
      (node (ref "CAM") (pin "18") (pinfunction "18_18") (pintype "passive"))
      (node (ref "IC2") (pin "65") (pinfunction "PC8_65") (pintype "bidirectional"))
    )
    (net (code "59") (name "OV7670_WRST") (class "Default")
      (node (ref "CAM") (pin "3") (pinfunction "3_3") (pintype "passive"))
      (node (ref "IC2") (pin "80") (pinfunction "PC12_80") (pintype "bidirectional"))
    )
    (net (code "60") (name "RA_IN") (class "Default")
      (node (ref "IC1") (pin "39") (pinfunction "RIGHT_39") (pintype "bidirectional"))
      (node (ref "JK1") (pin "2") (pinfunction "P$2_2") (pintype "bidirectional"))
      (node (ref "R14") (pin "2") (pinfunction "2_2") (pintype "passive"))
    )
    (net (code "61") (name "SD_CS") (class "Default")
      (node (ref "DISP") (pin "32") (pinfunction "32_32") (pintype "passive"))
      (node (ref "IC2") (pin "51") (pinfunction "PB12_51") (pintype "bidirectional"))
    )
    (net (code "62") (name "SW1") (class "Default")
      (node (ref "BUTTON4") (pin "2") (pinfunction "2_2") (pintype "passive"))
      (node (ref "IC2") (pin "68") (pinfunction "PA9_68") (pintype "bidirectional"))
    )
    (net (code "63") (name "SW2") (class "Default")
      (node (ref "BUTTON3") (pin "2") (pinfunction "2_2") (pintype "passive"))
      (node (ref "IC2") (pin "69") (pinfunction "PA10_69") (pintype "bidirectional"))
    )
    (net (code "64") (name "SW4") (class "Default")
      (node (ref "BUTTON1") (pin "2") (pinfunction "2_2") (pintype "passive"))
      (node (ref "IC2") (pin "77") (pinfunction "PA15_77") (pintype "bidirectional"))
    )
    (net (code "65") (name "SWCLK") (class "Default")
      (node (ref "BUTTON2") (pin "2") (pinfunction "2_2") (pintype "passive"))
      (node (ref "IC2") (pin "76") (pinfunction "PA14_76") (pintype "bidirectional"))
      (node (ref "ISP") (pin "3") (pinfunction "3_3") (pintype "passive"))
    )
    (net (code "66") (name "SWDIO") (class "Default")
      (node (ref "IC2") (pin "72") (pinfunction "PA13_72") (pintype "bidirectional"))
      (node (ref "ISP") (pin "4") (pinfunction "4_4") (pintype "passive"))
    )
    (net (code "67") (name "TFT_BL_EN") (class "Default")
      (node (ref "DISP") (pin "24") (pinfunction "24_24") (pintype "passive"))
      (node (ref "IC2") (pin "67") (pinfunction "PA8_67") (pintype "bidirectional"))
    )
    (net (code "68") (name "TFT_CS") (class "Default")
      (node (ref "DISP") (pin "19") (pinfunction "19_19") (pintype "passive"))
      (node (ref "IC2") (pin "88") (pinfunction "PD7_88") (pintype "bidirectional"))
    )
    (net (code "69") (name "TFT_D0") (class "Default")
      (node (ref "DISP") (pin "3") (pinfunction "3_3") (pintype "passive"))
      (node (ref "IC2") (pin "61") (pinfunction "PD14_61") (pintype "bidirectional"))
    )
    (net (code "70") (name "TFT_D1") (class "Default")
      (node (ref "DISP") (pin "4") (pinfunction "4_4") (pintype "passive"))
      (node (ref "IC2") (pin "62") (pinfunction "PD15_62") (pintype "bidirectional"))
    )
    (net (code "71") (name "TFT_D2") (class "Default")
      (node (ref "DISP") (pin "5") (pinfunction "5_5") (pintype "passive"))
      (node (ref "IC2") (pin "81") (pinfunction "PD0_81") (pintype "bidirectional"))
    )
    (net (code "72") (name "TFT_D3") (class "Default")
      (node (ref "DISP") (pin "6") (pinfunction "6_6") (pintype "passive"))
      (node (ref "IC2") (pin "82") (pinfunction "PD1_82") (pintype "bidirectional"))
    )
    (net (code "73") (name "TFT_D4") (class "Default")
      (node (ref "DISP") (pin "7") (pinfunction "7_7") (pintype "passive"))
      (node (ref "IC2") (pin "38") (pinfunction "PE7_38") (pintype "bidirectional"))
    )
    (net (code "74") (name "TFT_D5") (class "Default")
      (node (ref "DISP") (pin "8") (pinfunction "8_8") (pintype "passive"))
      (node (ref "IC2") (pin "39") (pinfunction "PE8_39") (pintype "bidirectional"))
    )
    (net (code "75") (name "TFT_D6") (class "Default")
      (node (ref "DISP") (pin "9") (pinfunction "9_9") (pintype "passive"))
      (node (ref "IC2") (pin "40") (pinfunction "PE9_40") (pintype "bidirectional"))
    )
    (net (code "76") (name "TFT_D7") (class "Default")
      (node (ref "DISP") (pin "10") (pinfunction "10_10") (pintype "passive"))
      (node (ref "IC2") (pin "41") (pinfunction "PE10_41") (pintype "bidirectional"))
    )
    (net (code "77") (name "TFT_D8") (class "Default")
      (node (ref "DISP") (pin "11") (pinfunction "11_11") (pintype "passive"))
      (node (ref "IC2") (pin "42") (pinfunction "PE11_42") (pintype "bidirectional"))
    )
    (net (code "78") (name "TFT_D9") (class "Default")
      (node (ref "DISP") (pin "12") (pinfunction "12_12") (pintype "passive"))
      (node (ref "IC2") (pin "43") (pinfunction "PE12_43") (pintype "bidirectional"))
    )
    (net (code "79") (name "TFT_D10") (class "Default")
      (node (ref "DISP") (pin "13") (pinfunction "13_13") (pintype "passive"))
      (node (ref "IC2") (pin "44") (pinfunction "PE13_44") (pintype "bidirectional"))
    )
    (net (code "80") (name "TFT_D11") (class "Default")
      (node (ref "DISP") (pin "14") (pinfunction "14_14") (pintype "passive"))
      (node (ref "IC2") (pin "45") (pinfunction "PE14_45") (pintype "bidirectional"))
    )
    (net (code "81") (name "TFT_D12") (class "Default")
      (node (ref "DISP") (pin "15") (pinfunction "15_15") (pintype "passive"))
      (node (ref "IC2") (pin "46") (pinfunction "PE15_46") (pintype "bidirectional"))
    )
    (net (code "82") (name "TFT_D13") (class "Default")
      (node (ref "DISP") (pin "16") (pinfunction "16_16") (pintype "passive"))
      (node (ref "IC2") (pin "55") (pinfunction "PD8_55") (pintype "bidirectional"))
    )
    (net (code "83") (name "TFT_D14") (class "Default")
      (node (ref "DISP") (pin "17") (pinfunction "17_17") (pintype "passive"))
      (node (ref "IC2") (pin "56") (pinfunction "PD9_56") (pintype "bidirectional"))
    )
    (net (code "84") (name "TFT_D15") (class "Default")
      (node (ref "DISP") (pin "18") (pinfunction "18_18") (pintype "passive"))
      (node (ref "IC2") (pin "57") (pinfunction "PD10_57") (pintype "bidirectional"))
    )
    (net (code "85") (name "TFT_RD") (class "Default")
      (node (ref "DISP") (pin "22") (pinfunction "22_22") (pintype "passive"))
      (node (ref "IC2") (pin "85") (pinfunction "PD4_85") (pintype "bidirectional"))
    )
    (net (code "86") (name "TFT_RS") (class "Default")
      (node (ref "DISP") (pin "20") (pinfunction "20_20") (pintype "passive"))
      (node (ref "IC2") (pin "58") (pinfunction "PD11_58") (pintype "bidirectional"))
    )
    (net (code "87") (name "TFT_WR") (class "Default")
      (node (ref "DISP") (pin "21") (pinfunction "21_21") (pintype "passive"))
      (node (ref "IC2") (pin "86") (pinfunction "PD5_86") (pintype "bidirectional"))
    )
    (net (code "88") (name "TP_CS") (class "Default")
      (node (ref "DISP") (pin "31") (pinfunction "31_31") (pintype "passive"))
      (node (ref "IC2") (pin "48") (pinfunction "PB11_48") (pintype "bidirectional"))
    )
    (net (code "89") (name "TP_SD_MISO") (class "Default")
      (node (ref "DISP") (pin "25") (pinfunction "25_25") (pintype "passive"))
      (node (ref "IC2") (pin "53") (pinfunction "PB14_53") (pintype "bidirectional"))
    )
    (net (code "90") (name "TP_SD_MOSI") (class "Default")
      (node (ref "DISP") (pin "27") (pinfunction "27_27") (pintype "passive"))
      (node (ref "IC2") (pin "54") (pinfunction "PB15_54") (pintype "bidirectional"))
    )
    (net (code "91") (name "TP_SD_SCLK") (class "Default")
      (node (ref "DISP") (pin "29") (pinfunction "29_29") (pintype "passive"))
      (node (ref "IC2") (pin "52") (pinfunction "PB13_52") (pintype "bidirectional"))
    )
    (net (code "92") (name "VBAT") (class "Default")
      (node (ref "IC2") (pin "6") (pinfunction "VBAT_6") (pintype "power_in"))
      (node (ref "U$1") (pin "+") (pinfunction "+_+") (pintype "bidirectional"))
    )
    (net (code "93") (name "VCC") (class "Default")
      (node (ref "C19") (pin "1") (pinfunction "1_1") (pintype "passive"))
      (node (ref "IC1") (pin "38") (pinfunction "AVDD_38") (pintype "power_in"))
      (node (ref "IC1") (pin "43") (pinfunction "AVDD1_43") (pintype "power_in"))
      (node (ref "IC1") (pin "45") (pinfunction "AVDD2_45") (pintype "power_in"))
      (node (ref "L2") (pin "2") (pinfunction "2_2") (pintype "passive"))
    )
    (net (code "94") (name "VS1003_CS") (class "Default")
      (node (ref "IC1") (pin "23") (pinfunction "XCS_23") (pintype "bidirectional"))
      (node (ref "IC2") (pin "29") (pinfunction "PA4_29") (pintype "bidirectional"))
    )
    (net (code "95") (name "VS1003_MISO") (class "Default")
      (node (ref "IC1") (pin "30") (pinfunction "SO_30") (pintype "bidirectional"))
      (node (ref "IC2") (pin "31") (pinfunction "PA6_31") (pintype "bidirectional"))
    )
    (net (code "96") (name "VS1003_MOSI") (class "Default")
      (node (ref "IC1") (pin "29") (pinfunction "SI_29") (pintype "bidirectional"))
      (node (ref "IC2") (pin "32") (pinfunction "PA7_32") (pintype "bidirectional"))
    )
    (net (code "97") (name "VS1003_SCK") (class "Default")
      (node (ref "IC1") (pin "28") (pinfunction "SCLK_28") (pintype "bidirectional"))
      (node (ref "IC2") (pin "30") (pinfunction "PA5_30") (pintype "bidirectional"))
    )
    (net (code "98") (name "XDCS") (class "Default")
      (node (ref "IC1") (pin "13") (pinfunction "XDCS/BSYNC_13") (pintype "bidirectional"))
      (node (ref "IC2") (pin "7") (pinfunction "PC13_7") (pintype "bidirectional"))
    )
    (net (code "99") (name "unconnected-(IC1A-GPIO1-Pad34)") (class "Default")
      (node (ref "IC1") (pin "34") (pinfunction "GPIO1_34") (pintype "bidirectional"))
    )
    (net (code "100") (name "unconnected-(IC1A-GPIO2{slash}DCLK-Pad9)") (class "Default")
      (node (ref "IC1") (pin "9") (pinfunction "GPIO2/DCLK_9") (pintype "bidirectional"))
    )
    (net (code "101") (name "unconnected-(IC1A-GPIO3{slash}SDATA-Pad10)") (class "Default")
      (node (ref "IC1") (pin "10") (pinfunction "GPIO3/SDATA_10") (pintype "bidirectional"))
    )
    (net (code "102") (name "unconnected-(IC1A-TX-Pad27)") (class "Default")
      (node (ref "IC1") (pin "27") (pinfunction "TX_27") (pintype "bidirectional"))
    )
    (net (code "103") (name "unconnected-(IC1A-VCO-Pad15)") (class "Default")
      (node (ref "IC1") (pin "15") (pinfunction "VCO_15") (pintype "bidirectional"))
    )
    (net (code "104") (name "unconnected-(IC2A-PA0-WKUP-Pad23)") (class "Default")
      (node (ref "IC2") (pin "23") (pinfunction "PA0-WKUP_23") (pintype "bidirectional"))
    )
    (net (code "105") (name "unconnected-(IC2A-PB1-Pad36)") (class "Default")
      (node (ref "IC2") (pin "36") (pinfunction "PB1_36") (pintype "bidirectional"))
    )
    (net (code "106") (name "unconnected-(IC2A-PB3-Pad89)") (class "Default")
      (node (ref "IC2") (pin "89") (pinfunction "PB3_89") (pintype "bidirectional"))
    )
    (net (code "107") (name "unconnected-(IC2A-PB4-Pad90)") (class "Default")
      (node (ref "IC2") (pin "90") (pinfunction "PB4_90") (pintype "bidirectional"))
    )
    (net (code "108") (name "unconnected-(IC2A-PB5-Pad91)") (class "Default")
      (node (ref "IC2") (pin "91") (pinfunction "PB5_91") (pintype "bidirectional"))
    )
    (net (code "109") (name "unconnected-(IC2A-PB8-Pad95)") (class "Default")
      (node (ref "IC2") (pin "95") (pinfunction "PB8_95") (pintype "bidirectional"))
    )
    (net (code "110") (name "unconnected-(IC2A-PB9-Pad96)") (class "Default")
      (node (ref "IC2") (pin "96") (pinfunction "PB9_96") (pintype "bidirectional"))
    )
    (net (code "111") (name "unconnected-(IC2A-PD2-Pad83)") (class "Default")
      (node (ref "IC2") (pin "83") (pinfunction "PD2_83") (pintype "bidirectional"))
    )
    (net (code "112") (name "unconnected-(IC2A-PD3-Pad84)") (class "Default")
      (node (ref "IC2") (pin "84") (pinfunction "PD3_84") (pintype "bidirectional"))
    )
    (net (code "113") (name "unconnected-(IC2A-PD6-Pad87)") (class "Default")
      (node (ref "IC2") (pin "87") (pinfunction "PD6_87") (pintype "bidirectional"))
    )
    (net (code "114") (name "unconnected-(IC2A-PD12-Pad59)") (class "Default")
      (node (ref "IC2") (pin "59") (pinfunction "PD12_59") (pintype "bidirectional"))
    )
    (net (code "115") (name "unconnected-(IC2A-PD13-Pad60)") (class "Default")
      (node (ref "IC2") (pin "60") (pinfunction "PD13_60") (pintype "bidirectional"))
    )
    (net (code "116") (name "unconnected-(IC2A-PE0-Pad97)") (class "Default")
      (node (ref "IC2") (pin "97") (pinfunction "PE0_97") (pintype "bidirectional"))
    )
    (net (code "117") (name "unconnected-(IC2A-PE1-Pad98)") (class "Default")
      (node (ref "IC2") (pin "98") (pinfunction "PE1_98") (pintype "bidirectional"))
    )
    (net (code "118") (name "unconnected-(IC2A-PE2-Pad1)") (class "Default")
      (node (ref "IC2") (pin "1") (pinfunction "PE2_1") (pintype "bidirectional"))
    )
    (net (code "119") (name "unconnected-(IC2A-PE3-Pad2)") (class "Default")
      (node (ref "IC2") (pin "2") (pinfunction "PE3_2") (pintype "bidirectional"))
    )
    (net (code "120") (name "unconnected-(IC2A-PE4-Pad3)") (class "Default")
      (node (ref "IC2") (pin "3") (pinfunction "PE4_3") (pintype "bidirectional"))
    )
    (net (code "121") (name "unconnected-(IC2A-PE5-Pad4)") (class "Default")
      (node (ref "IC2") (pin "4") (pinfunction "PE5_4") (pintype "bidirectional"))
    )
    (net (code "122") (name "unconnected-(IC2A-PE6-Pad5)") (class "Default")
      (node (ref "IC2") (pin "5") (pinfunction "PE6_5") (pintype "bidirectional"))
    )
  )
)
